# 05_LMS7002M_RF1.net
KiCad netlist of a schematic drawn in Altium Designer
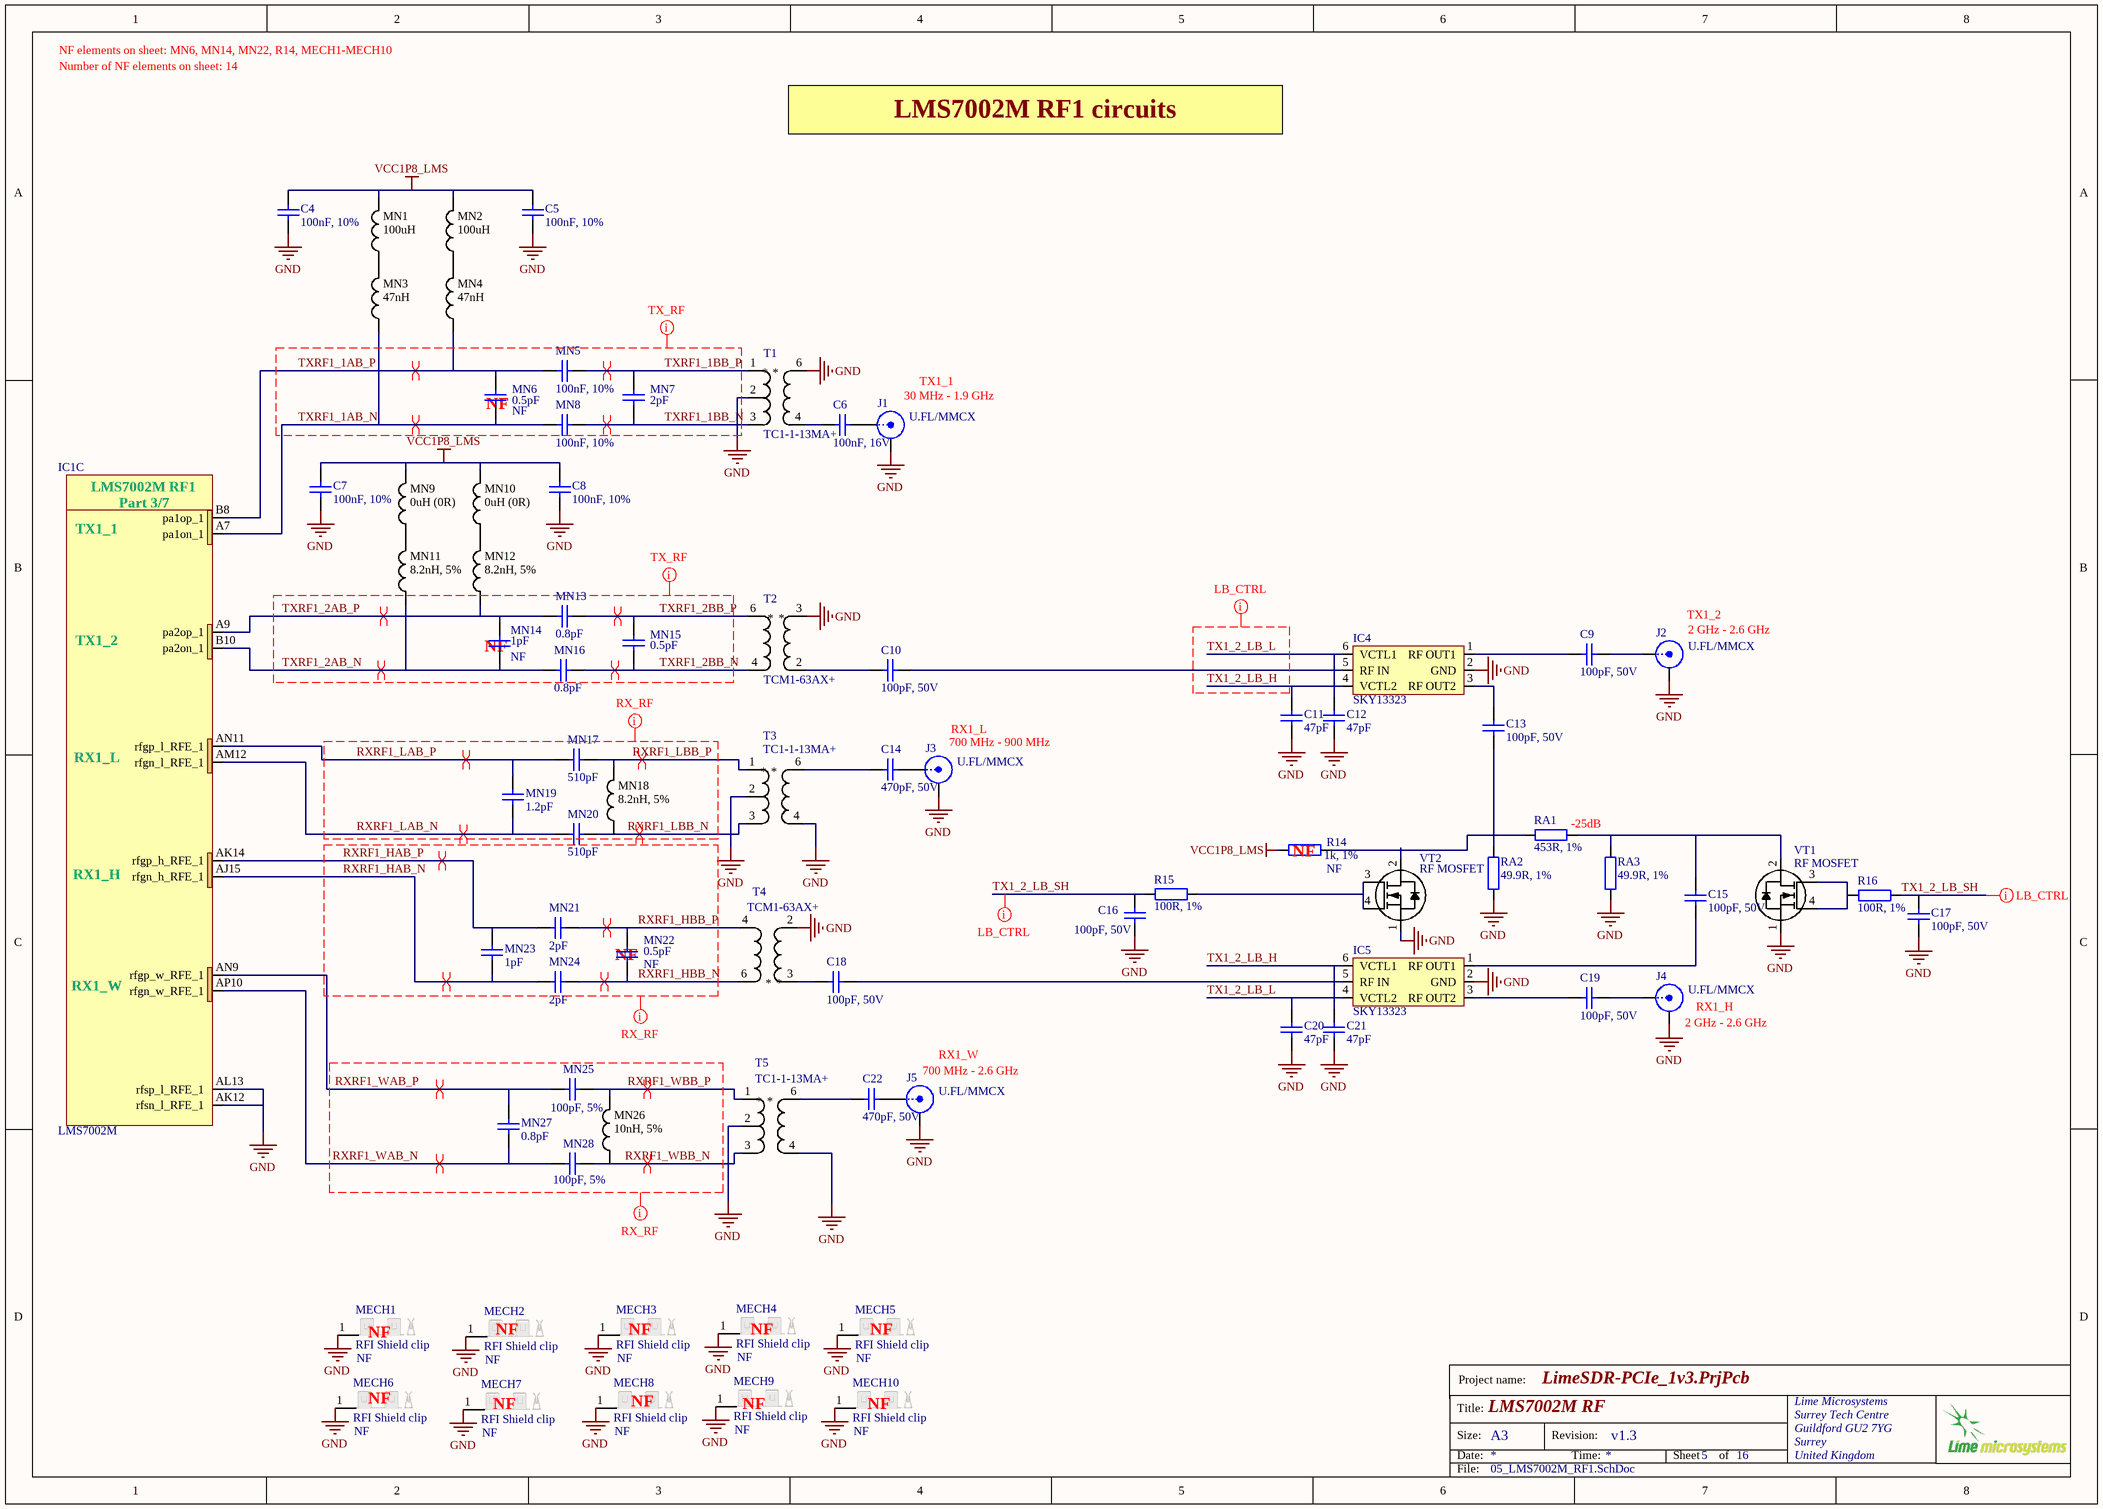
[diagram p0: 05_LMS7002M_RF1.SchDoc]

(export (version "E")
  (design (tool "Eeschema 10.0.6"))
  (components
    (comp (ref "C4")
      (value "100nF, 10%")
      (footprint "CAP0402")
      (fields
        (field (name "MANUFACTURER") "Murata Electronics")
        (field (name "TOLERANCE") "10 %")
        (field (name "MANUFACTURER PART NUMBER") "GRM155R71C104KA88D")
      )
      (libsource (lib "LimeMicroAltiumLib_schLib") (part "Cap_0402"))
    )
    (comp (ref "C5")
      (value "100nF, 10%")
      (footprint "CAP0402")
      (fields
        (field (name "MANUFACTURER") "Murata Electronics")
        (field (name "TOLERANCE") "10 %")
        (field (name "MANUFACTURER PART NUMBER") "GRM155R71C104KA88D")
      )
      (libsource (lib "LimeMicroAltiumLib_schLib") (part "Cap_0402"))
    )
    (comp (ref "C6")
      (value "100nF, 16V")
      (footprint "CAP0402")
      (fields
        (field (name "MANUFACTURER") "Murata Electronics")
        (field (name "TOLERANCE") "10 %")
        (field (name "MANUFACTURER PART NUMBER") "GRM155R71C104KA88D")
      )
      (libsource (lib "LimeMicroAltiumLib_schLib") (part "Cap_0402"))
    )
    (comp (ref "C7")
      (value "100nF, 10%")
      (footprint "CAP0402")
      (fields
        (field (name "MANUFACTURER") "Murata Electronics")
        (field (name "TOLERANCE") "10 %")
        (field (name "MANUFACTURER PART NUMBER") "GRM155R71C104KA88D")
      )
      (libsource (lib "LimeMicroAltiumLib_schLib") (part "Cap_0402"))
    )
    (comp (ref "C8")
      (value "100nF, 10%")
      (footprint "CAP0402")
      (fields
        (field (name "MANUFACTURER") "Murata Electronics")
        (field (name "TOLERANCE") "10 %")
        (field (name "MANUFACTURER PART NUMBER") "GRM155R71C104KA88D")
      )
      (libsource (lib "LimeMicroAltiumLib_schLib") (part "Cap_0402"))
    )
    (comp (ref "C9")
      (value "100pF, 50V")
      (footprint "CAP0402")
      (fields (field (name "TOLERANCE") "±5%") (field (name "MANUFACTURER") "Yageo"))
      (libsource (lib "LimeMicroAltiumLib_schLib") (part "Cap_0402"))
    )
    (comp (ref "C10")
      (value "100pF, 50V")
      (footprint "CAP0402")
      (fields (field (name "TOLERANCE") "±5%") (field (name "MANUFACTURER") "Yageo"))
      (libsource (lib "LimeMicroAltiumLib_schLib") (part "Cap_0402"))
    )
    (comp (ref "C11")
      (value "47pF")
      (footprint "CAP0402")
      (fields (field (name "TOLERANCE") "±1%") (field (name "MANUFACTURER") "TDK Corporation"))
      (libsource (lib "LimeMicroAltiumLib_schLib") (part "Cap_0402"))
    )
    (comp (ref "C12")
      (value "47pF")
      (footprint "CAP0402")
      (fields (field (name "TOLERANCE") "±1%") (field (name "MANUFACTURER") "TDK Corporation"))
      (libsource (lib "LimeMicroAltiumLib_schLib") (part "Cap_0402"))
    )
    (comp (ref "C13")
      (value "100pF, 50V")
      (footprint "CAP0402")
      (fields (field (name "TOLERANCE") "±5%") (field (name "MANUFACTURER") "Yageo"))
      (libsource (lib "LimeMicroAltiumLib_schLib") (part "Cap_0402"))
    )
    (comp (ref "C14")
      (value "470pF, 50V")
      (footprint "CAP0402")
      (fields
        (field (name "MANUFACTURER PART NUMBER") "C1005C0G1H471J050BA")
        (field (name "TOLERANCE") "±5%")
        (field (name "MANUFACTURER") "TDK Corporation")
      )
      (libsource (lib "LimeMicroAltiumLib_schLib") (part "Cap_0402"))
    )
    (comp (ref "C15")
      (value "100pF, 50V")
      (footprint "CAP0402")
      (fields (field (name "TOLERANCE") "±5%") (field (name "MANUFACTURER") "Yageo"))
      (libsource (lib "LimeMicroAltiumLib_schLib") (part "Cap_0402"))
    )
    (comp (ref "C16")
      (value "100pF, 50V")
      (footprint "CAP0402")
      (fields (field (name "TOLERANCE") "±5%") (field (name "MANUFACTURER") "Yageo"))
      (libsource (lib "LimeMicroAltiumLib_schLib") (part "Cap_0402"))
    )
    (comp (ref "C17")
      (value "100pF, 50V")
      (footprint "CAP0402")
      (fields (field (name "TOLERANCE") "±5%") (field (name "MANUFACTURER") "Yageo"))
      (libsource (lib "LimeMicroAltiumLib_schLib") (part "Cap_0402"))
    )
    (comp (ref "C18")
      (value "100pF, 50V")
      (footprint "CAP0402")
      (fields (field (name "TOLERANCE") "±5%") (field (name "MANUFACTURER") "Yageo"))
      (libsource (lib "LimeMicroAltiumLib_schLib") (part "Cap_0402"))
    )
    (comp (ref "C19")
      (value "100pF, 50V")
      (footprint "CAP0402")
      (fields (field (name "TOLERANCE") "±5%") (field (name "MANUFACTURER") "Yageo"))
      (libsource (lib "LimeMicroAltiumLib_schLib") (part "Cap_0402"))
    )
    (comp (ref "C20")
      (value "47pF")
      (footprint "CAP0402")
      (fields (field (name "TOLERANCE") "±1%") (field (name "MANUFACTURER") "TDK Corporation"))
      (libsource (lib "LimeMicroAltiumLib_schLib") (part "Cap_0402"))
    )
    (comp (ref "C21")
      (value "47pF")
      (footprint "CAP0402")
      (fields (field (name "TOLERANCE") "±1%") (field (name "MANUFACTURER") "TDK Corporation"))
      (libsource (lib "LimeMicroAltiumLib_schLib") (part "Cap_0402"))
    )
    (comp (ref "C22")
      (value "470pF, 50V")
      (footprint "CAP0402")
      (fields
        (field (name "MANUFACTURER PART NUMBER") "C1005C0G1H471J050BA")
        (field (name "TOLERANCE") "±5%")
        (field (name "MANUFACTURER") "TDK Corporation")
      )
      (libsource (lib "LimeMicroAltiumLib_schLib") (part "Cap_0402"))
    )
    (comp (ref "IC1")
      (value "LMS7002M")
      (footprint "LMS7002M_v2")
      (description "Schematic symbol revision 3. Default footprint - 0.31mm pad")
      (fields (field (name "MANUFACTURER") "Lime Microsystems"))
      (libsource (lib "LimeMicroAltiumLib_schLib") (part "LMS7002Mr3"))
    )
    (comp (ref "IC4")
      (value "SKY13323")
      (footprint "SKY13323-378LF")
      (description "SKY13323-378LF: 0.1-3.0 GHz GaAs SPDT Switch")
      (fields (field (name "MANUFACTURER") "Skyworks Solutions Inc."))
      (libsource (lib "LimeMicroAltiumLib_schLib") (part "SKY13323"))
    )
    (comp (ref "IC5")
      (value "SKY13323")
      (footprint "SKY13323-378LF")
      (description "SKY13323-378LF: 0.1-3.0 GHz GaAs SPDT Switch")
      (fields (field (name "MANUFACTURER") "Skyworks Solutions Inc."))
      (libsource (lib "LimeMicroAltiumLib_schLib") (part "SKY13323"))
    )
    (comp (ref "J1")
      (value "U.FL/MMCX")
      (footprint "MMCX_UFL_conn_u")
      (description "CONN UMC RCPT STR 50 OHM SMD")
      (fields (field (name "MANUFACTURER") "Molex, LLC"))
      (libsource (lib "LimeMicroAltiumLib_schLib") (part "RF_IF_connector"))
    )
    (comp (ref "J2")
      (value "U.FL/MMCX")
      (footprint "MMCX_UFL_conn_u")
      (description "CONN UMC RCPT STR 50 OHM SMD")
      (fields (field (name "MANUFACTURER") "Molex, LLC"))
      (libsource (lib "LimeMicroAltiumLib_schLib") (part "RF_IF_connector"))
    )
    (comp (ref "J3")
      (value "U.FL/MMCX")
      (footprint "MMCX_UFL_conn_u")
      (description "CONN UMC RCPT STR 50 OHM SMD")
      (fields (field (name "MANUFACTURER") "Molex, LLC"))
      (libsource (lib "LimeMicroAltiumLib_schLib") (part "RF_IF_connector"))
    )
    (comp (ref "J4")
      (value "U.FL/MMCX")
      (footprint "MMCX_UFL_conn_u")
      (description "CONN UMC RCPT STR 50 OHM SMD")
      (fields (field (name "MANUFACTURER") "Molex, LLC"))
      (libsource (lib "LimeMicroAltiumLib_schLib") (part "RF_IF_connector"))
    )
    (comp (ref "J5")
      (value "U.FL/MMCX")
      (footprint "MMCX_UFL_conn_u")
      (description "CONN UMC RCPT STR 50 OHM SMD")
      (fields (field (name "MANUFACTURER") "Molex, LLC"))
      (libsource (lib "LimeMicroAltiumLib_schLib") (part "RF_IF_connector"))
    )
    (comp (ref "MECH1")
      (value "RFI Shield clip")
      (footprint "RFI_SHIELD_CLPS_MINI")
      (fields (field (name "MANUFACTURER") "HARWIN") (field (name "ASSEMBLY INFO") "NF"))
      (libsource (lib "LimeMicroAltiumLib_schLib") (part "RFI_SHIELD_CLIP"))
    )
    (comp (ref "MECH2")
      (value "RFI Shield clip")
      (footprint "RFI_SHIELD_CLPS_MINI")
      (fields (field (name "MANUFACTURER") "HARWIN") (field (name "ASSEMBLY INFO") "NF"))
      (libsource (lib "LimeMicroAltiumLib_schLib") (part "RFI_SHIELD_CLIP"))
    )
    (comp (ref "MECH3")
      (value "RFI Shield clip")
      (footprint "RFI_SHIELD_CLPS_MINI")
      (fields (field (name "MANUFACTURER") "HARWIN") (field (name "ASSEMBLY INFO") "NF"))
      (libsource (lib "LimeMicroAltiumLib_schLib") (part "RFI_SHIELD_CLIP"))
    )
    (comp (ref "MECH4")
      (value "RFI Shield clip")
      (footprint "RFI_SHIELD_CLPS_MINI")
      (fields (field (name "MANUFACTURER") "HARWIN") (field (name "ASSEMBLY INFO") "NF"))
      (libsource (lib "LimeMicroAltiumLib_schLib") (part "RFI_SHIELD_CLIP"))
    )
    (comp (ref "MECH5")
      (value "RFI Shield clip")
      (footprint "RFI_SHIELD_CLPS_MINI")
      (fields (field (name "MANUFACTURER") "HARWIN") (field (name "ASSEMBLY INFO") "NF"))
      (libsource (lib "LimeMicroAltiumLib_schLib") (part "RFI_SHIELD_CLIP"))
    )
    (comp (ref "MECH6")
      (value "RFI Shield clip")
      (footprint "RFI_SHIELD_CLPS_MINI")
      (fields (field (name "MANUFACTURER") "HARWIN") (field (name "ASSEMBLY INFO") "NF"))
      (libsource (lib "LimeMicroAltiumLib_schLib") (part "RFI_SHIELD_CLIP"))
    )
    (comp (ref "MECH7")
      (value "RFI Shield clip")
      (footprint "RFI_SHIELD_CLPS_MINI")
      (fields (field (name "MANUFACTURER") "HARWIN") (field (name "ASSEMBLY INFO") "NF"))
      (libsource (lib "LimeMicroAltiumLib_schLib") (part "RFI_SHIELD_CLIP"))
    )
    (comp (ref "MECH8")
      (value "RFI Shield clip")
      (footprint "RFI_SHIELD_CLPS_MINI")
      (fields (field (name "MANUFACTURER") "HARWIN") (field (name "ASSEMBLY INFO") "NF"))
      (libsource (lib "LimeMicroAltiumLib_schLib") (part "RFI_SHIELD_CLIP"))
    )
    (comp (ref "MECH9")
      (value "RFI Shield clip")
      (footprint "RFI_SHIELD_CLPS_MINI")
      (fields (field (name "MANUFACTURER") "HARWIN") (field (name "ASSEMBLY INFO") "NF"))
      (libsource (lib "LimeMicroAltiumLib_schLib") (part "RFI_SHIELD_CLIP"))
    )
    (comp (ref "MECH10")
      (value "RFI Shield clip")
      (footprint "RFI_SHIELD_CLPS_MINI")
      (fields (field (name "MANUFACTURER") "HARWIN") (field (name "ASSEMBLY INFO") "NF"))
      (libsource (lib "LimeMicroAltiumLib_schLib") (part "RFI_SHIELD_CLIP"))
    )
    (comp (ref "MN1")
      (value "100uH")
      (footprint "RES0805")
      (fields
        (field (name "TOLERANCE") "±10%")
        (field (name "MANUFACTURER") "TDK Corporation")
        (field (name "MANUFACTURER PART NUMBER") "MLF2012C101KT000")
      )
      (libsource (lib "LimeMicroAltiumLib_schLib") (part "Inductor_0603"))
    )
    (comp (ref "MN2")
      (value "100uH")
      (footprint "RES0805")
      (fields
        (field (name "TOLERANCE") "±10%")
        (field (name "MANUFACTURER") "TDK Corporation")
        (field (name "MANUFACTURER PART NUMBER") "MLF2012C101KT000")
      )
      (libsource (lib "LimeMicroAltiumLib_schLib") (part "Inductor_0603"))
    )
    (comp (ref "MN3")
      (value "47nH")
      (footprint "RES0402")
      (fields
        (field (name "MANUFACTURER") "COILCRAFT")
        (field (name "MANUFACTURER PART NUMBER") "0402HP-47NXJLU")
      )
      (libsource (lib "LimeMicroAltiumLib_schLib") (part "Inductor_0603"))
    )
    (comp (ref "MN4")
      (value "47nH")
      (footprint "RES0402")
      (fields
        (field (name "MANUFACTURER") "COILCRAFT")
        (field (name "MANUFACTURER PART NUMBER") "0402HP-47NXJLU")
      )
      (libsource (lib "LimeMicroAltiumLib_schLib") (part "Inductor_0603"))
    )
    (comp (ref "MN5")
      (value "100nF, 10%")
      (footprint "CAP0402")
      (fields
        (field (name "MANUFACTURER") "Murata Electronics")
        (field (name "TOLERANCE") "10 %")
        (field (name "MANUFACTURER PART NUMBER") "GRM155R71C104KA88D")
      )
      (libsource (lib "LimeMicroAltiumLib_schLib") (part "Cap_0402"))
    )
    (comp (ref "MN6")
      (value "0.5pF")
      (footprint "CAP0402")
      (fields
        (field (name "ASSEMBLY INFO") "NF")
        (field (name "TOLERANCE") "±0.25pF")
        (field (name "MANUFACTURER") "Yageo")
      )
      (libsource (lib "LimeMicroAltiumLib_schLib") (part "Cap_0402"))
    )
    (comp (ref "MN7")
      (value "2pF")
      (footprint "CAP0402")
      (fields (field (name "MANUFACTURER PART NUMBER") "04025U2R0BAT2A") (field (name "MANUFACTURER") "AVX"))
      (libsource (lib "LimeMicroAltiumLib_schLib") (part "Cap_0402"))
    )
    (comp (ref "MN8")
      (value "100nF, 10%")
      (footprint "CAP0402")
      (fields
        (field (name "MANUFACTURER") "Murata Electronics")
        (field (name "TOLERANCE") "10 %")
        (field (name "MANUFACTURER PART NUMBER") "GRM155R71C104KA88D")
      )
      (libsource (lib "LimeMicroAltiumLib_schLib") (part "Cap_0402"))
    )
    (comp (ref "MN9")
      (value "0uH (0R)")
      (footprint "RES0805")
      (fields
        (field (name "MANUFACTURER") "BOURNS")
        (field (name "MANUFACTURER PART NUMBER") "CR0805-J/-000ELF")
      )
      (libsource (lib "LimeMicroAltiumLib_schLib") (part "Inductor_0603"))
    )
    (comp (ref "MN10")
      (value "0uH (0R)")
      (footprint "RES0805")
      (fields
        (field (name "MANUFACTURER") "BOURNS")
        (field (name "MANUFACTURER PART NUMBER") "CR0805-J/-000ELF")
      )
      (libsource (lib "LimeMicroAltiumLib_schLib") (part "Inductor_0603"))
    )
    (comp (ref "MN11")
      (value "8.2nH, 5%")
      (footprint "RES0402")
      (fields (field (name "MANUFACTURER") "COILCRAFT"))
      (libsource (lib "LimeMicroAltiumLib_schLib") (part "Inductor_0603"))
    )
    (comp (ref "MN12")
      (value "8.2nH, 5%")
      (footprint "RES0402")
      (fields (field (name "MANUFACTURER") "COILCRAFT"))
      (libsource (lib "LimeMicroAltiumLib_schLib") (part "Inductor_0603"))
    )
    (comp (ref "MN13")
      (value "0.8pF")
      (footprint "CAP0402")
      (fields
        (field (name "TOLERANCE") "±0.1pF")
        (field (name "MANUFACTURER") "Murata Electronics North America")
        (field (name "MANUFACTURER PART NUMBER") "GRM1555C1HR80BA01D")
      )
      (libsource (lib "LimeMicroAltiumLib_schLib") (part "Cap_0402"))
    )
    (comp (ref "MN14")
      (value "1pF")
      (footprint "CAP0402")
      (fields
        (field (name "ASSEMBLY INFO") "NF")
        (field (name "MANUFACTURER") "TDK Corporation")
        (field (name "TOLERANCE") "±0.1pF")
      )
      (libsource (lib "LimeMicroAltiumLib_schLib") (part "Cap_0402"))
    )
    (comp (ref "MN15")
      (value "0.5pF")
      (footprint "CAP0402")
      (fields (field (name "TOLERANCE") "±0.25pF") (field (name "MANUFACTURER") "Yageo"))
      (libsource (lib "LimeMicroAltiumLib_schLib") (part "Cap_0402"))
    )
    (comp (ref "MN16")
      (value "0.8pF")
      (footprint "CAP0402")
      (fields
        (field (name "TOLERANCE") "±0.1pF")
        (field (name "MANUFACTURER") "Murata Electronics North America")
        (field (name "MANUFACTURER PART NUMBER") "GRM1555C1HR80BA01D")
      )
      (libsource (lib "LimeMicroAltiumLib_schLib") (part "Cap_0402"))
    )
    (comp (ref "MN17")
      (value "510pF")
      (footprint "CAP0402")
      (fields
        (field (name "TOLERANCE") "±5%")
        (field (name "MANUFACTURER") "Murata Electronics North America")
        (field (name "MANUFACTURER PART NUMBER") "GRM1555C1H511JA01D")
      )
      (libsource (lib "LimeMicroAltiumLib_schLib") (part "Cap_0402"))
    )
    (comp (ref "MN18")
      (value "8.2nH, 5%")
      (footprint "RES0402")
      (fields (field (name "MANUFACTURER") "COILCRAFT"))
      (libsource (lib "LimeMicroAltiumLib_schLib") (part "Inductor_0603"))
    )
    (comp (ref "MN19")
      (value "1.2pF")
      (footprint "CAP0402")
      (fields
        (field (name "MANUFACTURER") "Murata Electronics North America")
        (field (name "MANUFACTURER PART NUMBER") "GRM1555C1H1R2CA01D")
        (field (name "TOLERANCE") "±0.25pF")
      )
      (libsource (lib "LimeMicroAltiumLib_schLib") (part "Cap_0402"))
    )
    (comp (ref "MN20")
      (value "510pF")
      (footprint "CAP0402")
      (fields
        (field (name "TOLERANCE") "±5%")
        (field (name "MANUFACTURER") "Murata Electronics North America")
        (field (name "MANUFACTURER PART NUMBER") "GRM1555C1H511JA01D")
      )
      (libsource (lib "LimeMicroAltiumLib_schLib") (part "Cap_0402"))
    )
    (comp (ref "MN21")
      (value "2pF")
      (footprint "CAP0402")
      (fields (field (name "MANUFACTURER PART NUMBER") "04025U2R0BAT2A") (field (name "MANUFACTURER") "AVX"))
      (libsource (lib "LimeMicroAltiumLib_schLib") (part "Cap_0402"))
    )
    (comp (ref "MN22")
      (value "0.5pF")
      (footprint "CAP0402")
      (fields
        (field (name "ASSEMBLY INFO") "NF")
        (field (name "TOLERANCE") "±0.25pF")
        (field (name "MANUFACTURER") "Yageo")
      )
      (libsource (lib "LimeMicroAltiumLib_schLib") (part "Cap_0402"))
    )
    (comp (ref "MN23")
      (value "1pF")
      (footprint "CAP0402")
      (fields (field (name "MANUFACTURER") "TDK Corporation") (field (name "TOLERANCE") "±0.1pF"))
      (libsource (lib "LimeMicroAltiumLib_schLib") (part "Cap_0402"))
    )
    (comp (ref "MN24")
      (value "2pF")
      (footprint "CAP0402")
      (fields (field (name "MANUFACTURER PART NUMBER") "04025U2R0BAT2A") (field (name "MANUFACTURER") "AVX"))
      (libsource (lib "LimeMicroAltiumLib_schLib") (part "Cap_0402"))
    )
    (comp (ref "MN25")
      (value "100pF, 5%")
      (footprint "CAP0402")
      (fields (field (name "TOLERANCE") "±5%") (field (name "MANUFACTURER") "Yageo"))
      (libsource (lib "LimeMicroAltiumLib_schLib") (part "Cap_0402"))
    )
    (comp (ref "MN26")
      (value "10nH, 5%")
      (footprint "RES0402")
      (fields (field (name "MANUFACTURER") "COILCRAFT"))
      (libsource (lib "LimeMicroAltiumLib_schLib") (part "Inductor_0603"))
    )
    (comp (ref "MN27")
      (value "0.8pF")
      (footprint "CAP0402")
      (fields
        (field (name "TOLERANCE") "±0.1pF")
        (field (name "MANUFACTURER") "Murata Electronics North America")
        (field (name "MANUFACTURER PART NUMBER") "GRM1555C1HR80BA01D")
      )
      (libsource (lib "LimeMicroAltiumLib_schLib") (part "Cap_0402"))
    )
    (comp (ref "MN28")
      (value "100pF, 5%")
      (footprint "CAP0402")
      (fields (field (name "TOLERANCE") "±5%") (field (name "MANUFACTURER") "Yageo"))
      (libsource (lib "LimeMicroAltiumLib_schLib") (part "Cap_0402"))
    )
    (comp (ref "R14")
      (value "1k, 1%")
      (footprint "RES0402")
      (fields
        (field (name "ASSEMBLY INFO") "NF")
        (field (name "MANUFACTURER") "Stackpole Electronics Inc")
        (field (name "TOLERANCE") "±1%")
      )
      (libsource (lib "LimeMicroAltiumLib_schLib") (part "Res_0402"))
    )
    (comp (ref "R15")
      (value "100R, 1%")
      (footprint "RES0402")
      (fields (field (name "TOLERANCE") "±1%") (field (name "MANUFACTURER") "Stackpole Electronics Inc."))
      (libsource (lib "LimeFPGAboard_schLib") (part "Res_0402"))
    )
    (comp (ref "R16")
      (value "100R, 1%")
      (footprint "RES0402")
      (fields (field (name "TOLERANCE") "±1%") (field (name "MANUFACTURER") "Stackpole Electronics Inc."))
      (libsource (lib "LimeFPGAboard_schLib") (part "Res_0402"))
    )
    (comp (ref "RA1")
      (value "453R, 1%")
      (footprint "RES0402")
      (fields (field (name "MANUFACTURER") "Yageo") (field (name "TOLERANCE") "±1%"))
      (libsource (lib "LimeMicroAltiumLib_schLib") (part "Res_0402"))
    )
    (comp (ref "RA2")
      (value "49.9R, 1%")
      (footprint "RES0402")
      (fields
        (field (name "TOLERANCE") "±1%")
        (field (name "MANUFACTURER") "Samsung Electro-Mechanics America, Inc.")
        (field (name "MANUFACTURER PART NUMBER") "RC1005F49R9CS")
      )
      (libsource (lib "LimeMicroAltiumLib_schLib") (part "Res_0402"))
    )
    (comp (ref "RA3")
      (value "49.9R, 1%")
      (footprint "RES0402")
      (fields
        (field (name "TOLERANCE") "±1%")
        (field (name "MANUFACTURER") "Samsung Electro-Mechanics America, Inc.")
        (field (name "MANUFACTURER PART NUMBER") "RC1005F49R9CS")
      )
      (libsource (lib "LimeMicroAltiumLib_schLib") (part "Res_0402"))
    )
    (comp (ref "T1")
      (value "TC1-1-13MA+")
      (footprint "TC1-1-13MA+_v2")
      (fields (field (name "MANUFACTURER") "Mini-Circuits"))
      (libsource (lib "LimeMicroAltiumLib_schLib") (part "Balun"))
    )
    (comp (ref "T2")
      (value "TCM1-63AX+")
      (footprint "TCM1-63AX+_v2")
      (fields (field (name "MANUFACTURER") "Mini-circuits"))
      (libsource (lib "LimeMicroAltiumLib_schLib") (part "Balun_v2"))
    )
    (comp (ref "T3")
      (value "TC1-1-13MA+")
      (footprint "TC1-1-13MA+_v2")
      (fields (field (name "MANUFACTURER") "Mini-Circuits"))
      (libsource (lib "LimeMicroAltiumLib_schLib") (part "Balun"))
    )
    (comp (ref "T4")
      (value "TCM1-63AX+")
      (footprint "TCM1-63AX+_v2")
      (fields (field (name "MANUFACTURER") "Mini-circuits"))
      (libsource (lib "") (part "Balun_v2_1"))
    )
    (comp (ref "T5")
      (value "TC1-1-13MA+")
      (footprint "TC1-1-13MA+_v2")
      (fields (field (name "MANUFACTURER") "Mini-Circuits"))
      (libsource (lib "LimeMicroAltiumLib_schLib") (part "Balun"))
    )
    (comp (ref "VT1")
      (value "RF MOSFET")
      (footprint "BF1105R_SOT143R4")
      (fields (field (name "MANUFACTURER") "NXP Semiconductors"))
      (libsource (lib "LimeMicroAltiumLib_schLib") (part "BF1105R,215"))
    )
    (comp (ref "VT2")
      (value "RF MOSFET")
      (footprint "BF1105R_SOT143R4")
      (fields (field (name "MANUFACTURER") "NXP Semiconductors"))
      (libsource (lib "LimeMicroAltiumLib_schLib") (part "BF1105R,215"))
    )
  )
  (nets
    (net (code "1") (name "/RXRF1_HAB_N") (class "Default")
      (node (ref "IC1") (pin "AJ15") (pinfunction "rfgn_h_RFE_1_AJ15") (pintype "passive"))
      (node (ref "MN23") (pin "1") (pinfunction "1_1") (pintype "passive"))
      (node (ref "MN24") (pin "2") (pinfunction "2_2") (pintype "passive"))
    )
    (net (code "2") (name "/RXRF1_HAB_P") (class "Default")
      (node (ref "IC1") (pin "AK14") (pinfunction "rfgp_h_RFE_1_AK14") (pintype "passive"))
      (node (ref "MN21") (pin "2") (pinfunction "2_2") (pintype "passive"))
      (node (ref "MN23") (pin "2") (pinfunction "2_2") (pintype "passive"))
    )
    (net (code "3") (name "/RXRF1_HBB_N") (class "Default")
      (node (ref "MN22") (pin "1") (pinfunction "1_1") (pintype "passive"))
      (node (ref "MN24") (pin "1") (pinfunction "1_1") (pintype "passive"))
      (node (ref "T4") (pin "6") (pinfunction "6_6") (pintype "passive"))
    )
    (net (code "4") (name "/RXRF1_HBB_P") (class "Default")
      (node (ref "MN21") (pin "1") (pinfunction "1_1") (pintype "passive"))
      (node (ref "MN22") (pin "2") (pinfunction "2_2") (pintype "passive"))
      (node (ref "T4") (pin "4") (pinfunction "4_4") (pintype "passive"))
    )
    (net (code "5") (name "/RXRF1_LAB_N") (class "Default")
      (node (ref "IC1") (pin "AM12") (pinfunction "rfgn_l_RFE_1_AM12") (pintype "passive"))
      (node (ref "MN19") (pin "1") (pinfunction "1_1") (pintype "passive"))
      (node (ref "MN20") (pin "2") (pinfunction "2_2") (pintype "passive"))
    )
    (net (code "6") (name "/RXRF1_LAB_P") (class "Default")
      (node (ref "IC1") (pin "AN11") (pinfunction "rfgp_l_RFE_1_AN11") (pintype "passive"))
      (node (ref "MN17") (pin "2") (pinfunction "2_2") (pintype "passive"))
      (node (ref "MN19") (pin "2") (pinfunction "2_2") (pintype "passive"))
    )
    (net (code "7") (name "/RXRF1_LBB_N") (class "Default")
      (node (ref "MN18") (pin "1") (pinfunction "1_1") (pintype "passive"))
      (node (ref "MN20") (pin "1") (pinfunction "1_1") (pintype "passive"))
      (node (ref "T3") (pin "3") (pinfunction "3_3") (pintype "passive"))
    )
    (net (code "8") (name "/RXRF1_LBB_P") (class "Default")
      (node (ref "MN17") (pin "1") (pinfunction "1_1") (pintype "passive"))
      (node (ref "MN18") (pin "2") (pinfunction "2_2") (pintype "passive"))
      (node (ref "T3") (pin "1") (pinfunction "1_1") (pintype "passive"))
    )
    (net (code "9") (name "/RXRF1_WAB_N") (class "Default")
      (node (ref "IC1") (pin "AP10") (pinfunction "rfgn_w_RFE_1_AP10") (pintype "passive"))
      (node (ref "MN27") (pin "2") (pinfunction "2_2") (pintype "passive"))
      (node (ref "MN28") (pin "2") (pinfunction "2_2") (pintype "passive"))
    )
    (net (code "10") (name "/RXRF1_WAB_P") (class "Default")
      (node (ref "IC1") (pin "AN9") (pinfunction "rfgp_w_RFE_1_AN9") (pintype "passive"))
      (node (ref "MN25") (pin "2") (pinfunction "2_2") (pintype "passive"))
      (node (ref "MN27") (pin "1") (pinfunction "1_1") (pintype "passive"))
    )
    (net (code "11") (name "/RXRF1_WBB_N") (class "Default")
      (node (ref "MN26") (pin "1") (pinfunction "1_1") (pintype "passive"))
      (node (ref "MN28") (pin "1") (pinfunction "1_1") (pintype "passive"))
      (node (ref "T5") (pin "3") (pinfunction "3_3") (pintype "passive"))
    )
    (net (code "12") (name "/RXRF1_WBB_P") (class "Default")
      (node (ref "MN25") (pin "1") (pinfunction "1_1") (pintype "passive"))
      (node (ref "MN26") (pin "2") (pinfunction "2_2") (pintype "passive"))
      (node (ref "T5") (pin "1") (pinfunction "1_1") (pintype "passive"))
    )
    (net (code "13") (name "/TX1_2_LB_H") (class "Default")
      (node (ref "C11") (pin "2") (pinfunction "2_2") (pintype "passive"))
      (node (ref "C21") (pin "2") (pinfunction "2_2") (pintype "passive"))
      (node (ref "IC4") (pin "4") (pinfunction "VCTL2_4") (pintype "input"))
      (node (ref "IC5") (pin "6") (pinfunction "VCTL1_6") (pintype "input"))
    )
    (net (code "14") (name "/TX1_2_LB_L") (class "Default")
      (node (ref "C12") (pin "2") (pinfunction "2_2") (pintype "passive"))
      (node (ref "C20") (pin "2") (pinfunction "2_2") (pintype "passive"))
      (node (ref "IC4") (pin "6") (pinfunction "VCTL1_6") (pintype "input"))
      (node (ref "IC5") (pin "4") (pinfunction "VCTL2_4") (pintype "input"))
    )
    (net (code "15") (name "/TX1_2_LB_SH") (class "Default")
      (node (ref "C16") (pin "1") (pinfunction "1_1") (pintype "passive"))
      (node (ref "C17") (pin "1") (pinfunction "1_1") (pintype "passive"))
      (node (ref "R15") (pin "2") (pinfunction "2_2") (pintype "passive"))
      (node (ref "R16") (pin "1") (pinfunction "1_1") (pintype "passive"))
    )
    (net (code "16") (name "/TXRF1_1AB_N") (class "Default")
      (node (ref "IC1") (pin "A7") (pinfunction "pa1on_1_A7") (pintype "passive"))
      (node (ref "MN3") (pin "1") (pinfunction "1_1") (pintype "passive"))
      (node (ref "MN6") (pin "1") (pinfunction "1_1") (pintype "passive"))
      (node (ref "MN8") (pin "1") (pinfunction "1_1") (pintype "passive"))
    )
    (net (code "17") (name "/TXRF1_1AB_P") (class "Default")
      (node (ref "IC1") (pin "B8") (pinfunction "pa1op_1_B8") (pintype "passive"))
      (node (ref "MN4") (pin "1") (pinfunction "1_1") (pintype "passive"))
      (node (ref "MN5") (pin "2") (pinfunction "2_2") (pintype "passive"))
      (node (ref "MN6") (pin "2") (pinfunction "2_2") (pintype "passive"))
    )
    (net (code "18") (name "/TXRF1_1BB_N") (class "Default")
      (node (ref "MN7") (pin "1") (pinfunction "1_1") (pintype "passive"))
      (node (ref "MN8") (pin "2") (pinfunction "2_2") (pintype "passive"))
      (node (ref "T1") (pin "3") (pinfunction "3_3") (pintype "passive"))
    )
    (net (code "19") (name "/TXRF1_1BB_P") (class "Default")
      (node (ref "MN5") (pin "1") (pinfunction "1_1") (pintype "passive"))
      (node (ref "MN7") (pin "2") (pinfunction "2_2") (pintype "passive"))
      (node (ref "T1") (pin "1") (pinfunction "1_1") (pintype "passive"))
    )
    (net (code "20") (name "/TXRF1_2AB_N") (class "Default")
      (node (ref "IC1") (pin "B10") (pinfunction "pa2on_1_B10") (pintype "passive"))
      (node (ref "MN11") (pin "1") (pinfunction "1_1") (pintype "passive"))
      (node (ref "MN14") (pin "2") (pinfunction "2_2") (pintype "passive"))
      (node (ref "MN16") (pin "2") (pinfunction "2_2") (pintype "passive"))
    )
    (net (code "21") (name "/TXRF1_2AB_P") (class "Default")
      (node (ref "IC1") (pin "A9") (pinfunction "pa2op_1_A9") (pintype "passive"))
      (node (ref "MN12") (pin "1") (pinfunction "1_1") (pintype "passive"))
      (node (ref "MN13") (pin "2") (pinfunction "2_2") (pintype "passive"))
      (node (ref "MN14") (pin "1") (pinfunction "1_1") (pintype "passive"))
    )
    (net (code "22") (name "/TXRF1_2BB_N") (class "Default")
      (node (ref "MN15") (pin "1") (pinfunction "1_1") (pintype "passive"))
      (node (ref "MN16") (pin "1") (pinfunction "1_1") (pintype "passive"))
      (node (ref "T2") (pin "4") (pinfunction "4_4") (pintype "passive"))
    )
    (net (code "23") (name "/TXRF1_2BB_P") (class "Default")
      (node (ref "MN13") (pin "1") (pinfunction "1_1") (pintype "passive"))
      (node (ref "MN15") (pin "2") (pinfunction "2_2") (pintype "passive"))
      (node (ref "T2") (pin "6") (pinfunction "6_6") (pintype "passive"))
    )
    (net (code "24") (name "GND") (class "Default")
      (node (ref "C11") (pin "1") (pinfunction "1_1") (pintype "passive"))
      (node (ref "C12") (pin "1") (pinfunction "1_1") (pintype "passive"))
      (node (ref "C16") (pin "2") (pinfunction "2_2") (pintype "passive"))
      (node (ref "C17") (pin "2") (pinfunction "2_2") (pintype "passive"))
      (node (ref "C20") (pin "1") (pinfunction "1_1") (pintype "passive"))
      (node (ref "C21") (pin "1") (pinfunction "1_1") (pintype "passive"))
      (node (ref "C4") (pin "1") (pinfunction "1_1") (pintype "passive"))
      (node (ref "C5") (pin "1") (pinfunction "1_1") (pintype "passive"))
      (node (ref "C7") (pin "1") (pinfunction "1_1") (pintype "passive"))
      (node (ref "C8") (pin "1") (pinfunction "1_1") (pintype "passive"))
      (node (ref "IC1") (pin "AK12") (pinfunction "rfsn_l_RFE_1_AK12") (pintype "passive"))
      (node (ref "IC1") (pin "AL13") (pinfunction "rfsp_l_RFE_1_AL13") (pintype "passive"))
      (node (ref "IC4") (pin "2") (pinfunction "GND_2") (pintype "passive"))
      (node (ref "IC5") (pin "2") (pinfunction "GND_2") (pintype "passive"))
      (node (ref "J1") (pin "2") (pinfunction "Y_2") (pintype "passive"))
      (node (ref "J2") (pin "2") (pinfunction "Y_2") (pintype "passive"))
      (node (ref "J3") (pin "2") (pinfunction "Y_2") (pintype "passive"))
      (node (ref "J4") (pin "2") (pinfunction "Y_2") (pintype "passive"))
      (node (ref "J5") (pin "2") (pinfunction "Y_2") (pintype "passive"))
      (node (ref "MECH1") (pin "1") (pinfunction "GND_1") (pintype "passive"))
      (node (ref "MECH10") (pin "1") (pinfunction "GND_1") (pintype "passive"))
      (node (ref "MECH2") (pin "1") (pinfunction "GND_1") (pintype "passive"))
      (node (ref "MECH3") (pin "1") (pinfunction "GND_1") (pintype "passive"))
      (node (ref "MECH4") (pin "1") (pinfunction "GND_1") (pintype "passive"))
      (node (ref "MECH5") (pin "1") (pinfunction "GND_1") (pintype "passive"))
      (node (ref "MECH6") (pin "1") (pinfunction "GND_1") (pintype "passive"))
      (node (ref "MECH7") (pin "1") (pinfunction "GND_1") (pintype "passive"))
      (node (ref "MECH8") (pin "1") (pinfunction "GND_1") (pintype "passive"))
      (node (ref "MECH9") (pin "1") (pinfunction "GND_1") (pintype "passive"))
      (node (ref "RA2") (pin "1") (pinfunction "1_1") (pintype "passive"))
      (node (ref "RA3") (pin "1") (pinfunction "1_1") (pintype "passive"))
      (node (ref "T1") (pin "2") (pinfunction "2_2") (pintype "passive"))
      (node (ref "T1") (pin "6") (pinfunction "6_6") (pintype "passive"))
      (node (ref "T2") (pin "3") (pinfunction "3_3") (pintype "passive"))
      (node (ref "T3") (pin "2") (pinfunction "2_2") (pintype "passive"))
      (node (ref "T3") (pin "4") (pinfunction "4_4") (pintype "passive"))
      (node (ref "T4") (pin "2") (pinfunction "2_2") (pintype "passive"))
      (node (ref "T5") (pin "2") (pinfunction "2_2") (pintype "passive"))
      (node (ref "T5") (pin "4") (pinfunction "4_4") (pintype "passive"))
      (node (ref "VT1") (pin "1") (pinfunction "S_1") (pintype "passive"))
      (node (ref "VT2") (pin "1") (pinfunction "S_1") (pintype "passive"))
    )
    (net (code "25") (name "Net-(C6-Pad2)") (class "Default")
      (node (ref "C6") (pin "2") (pinfunction "2_2") (pintype "passive"))
      (node (ref "T1") (pin "4") (pinfunction "4_4") (pintype "passive"))
    )
    (net (code "26") (name "Net-(C10-Pad2)") (class "Default")
      (node (ref "C10") (pin "2") (pinfunction "2_2") (pintype "passive"))
      (node (ref "T2") (pin "2") (pinfunction "2_2") (pintype "passive"))
    )
    (net (code "27") (name "Net-(C14-Pad2)") (class "Default")
      (node (ref "C14") (pin "2") (pinfunction "2_2") (pintype "passive"))
      (node (ref "T3") (pin "6") (pinfunction "6_6") (pintype "passive"))
    )
    (net (code "28") (name "Net-(C18-Pad2)") (class "Default")
      (node (ref "C18") (pin "2") (pinfunction "2_2") (pintype "passive"))
      (node (ref "T4") (pin "3") (pinfunction "3_3") (pintype "passive"))
    )
    (net (code "29") (name "Net-(C22-Pad2)") (class "Default")
      (node (ref "C22") (pin "2") (pinfunction "2_2") (pintype "passive"))
      (node (ref "T5") (pin "6") (pinfunction "6_6") (pintype "passive"))
    )
    (net (code "30") (name "Net-(IC4-RF_IN)") (class "Default")
      (node (ref "C10") (pin "1") (pinfunction "1_1") (pintype "passive"))
      (node (ref "IC4") (pin "5") (pinfunction "RF_IN_5") (pintype "input"))
    )
    (net (code "31") (name "Net-(IC4-RF_OUT1)") (class "Default")
      (node (ref "C9") (pin "2") (pinfunction "2_2") (pintype "passive"))
      (node (ref "IC4") (pin "1") (pinfunction "RF_OUT1_1") (pintype "output"))
    )
    (net (code "32") (name "Net-(IC4-RF_OUT2)") (class "Default")
      (node (ref "C13") (pin "1") (pinfunction "1_1") (pintype "passive"))
      (node (ref "IC4") (pin "3") (pinfunction "RF_OUT2_3") (pintype "output"))
    )
    (net (code "33") (name "Net-(IC5-RF_IN)") (class "Default")
      (node (ref "C18") (pin "1") (pinfunction "1_1") (pintype "passive"))
      (node (ref "IC5") (pin "5") (pinfunction "RF_IN_5") (pintype "input"))
    )
    (net (code "34") (name "Net-(IC5-RF_OUT1)") (class "Default")
      (node (ref "C15") (pin "2") (pinfunction "2_2") (pintype "passive"))
      (node (ref "IC5") (pin "1") (pinfunction "RF_OUT1_1") (pintype "output"))
    )
    (net (code "35") (name "Net-(IC5-RF_OUT2)") (class "Default")
      (node (ref "C19") (pin "2") (pinfunction "2_2") (pintype "passive"))
      (node (ref "IC5") (pin "3") (pinfunction "RF_OUT2_3") (pintype "output"))
    )
    (net (code "36") (name "Net-(J1-X)") (class "Default")
      (node (ref "C6") (pin "1") (pinfunction "1_1") (pintype "passive"))
      (node (ref "J1") (pin "1") (pinfunction "X_1") (pintype "passive"))
    )
    (net (code "37") (name "Net-(J2-X)") (class "Default")
      (node (ref "C9") (pin "1") (pinfunction "1_1") (pintype "passive"))
      (node (ref "J2") (pin "1") (pinfunction "X_1") (pintype "passive"))
    )
    (net (code "38") (name "Net-(J3-X)") (class "Default")
      (node (ref "C14") (pin "1") (pinfunction "1_1") (pintype "passive"))
      (node (ref "J3") (pin "1") (pinfunction "X_1") (pintype "passive"))
    )
    (net (code "39") (name "Net-(J4-X)") (class "Default")
      (node (ref "C19") (pin "1") (pinfunction "1_1") (pintype "passive"))
      (node (ref "J4") (pin "1") (pinfunction "X_1") (pintype "passive"))
    )
    (net (code "40") (name "Net-(J5-X)") (class "Default")
      (node (ref "C22") (pin "1") (pinfunction "1_1") (pintype "passive"))
      (node (ref "J5") (pin "1") (pinfunction "X_1") (pintype "passive"))
    )
    (net (code "41") (name "Net-(MN1-Pad1)") (class "Default")
      (node (ref "MN1") (pin "1") (pinfunction "1_1") (pintype "passive"))
      (node (ref "MN3") (pin "2") (pinfunction "2_2") (pintype "passive"))
    )
    (net (code "42") (name "Net-(MN2-Pad1)") (class "Default")
      (node (ref "MN2") (pin "1") (pinfunction "1_1") (pintype "passive"))
      (node (ref "MN4") (pin "2") (pinfunction "2_2") (pintype "passive"))
    )
    (net (code "43") (name "Net-(MN10-Pad1)") (class "Default")
      (node (ref "MN10") (pin "1") (pinfunction "1_1") (pintype "passive"))
      (node (ref "MN12") (pin "2") (pinfunction "2_2") (pintype "passive"))
    )
    (net (code "44") (name "Net-(MN11-Pad2)") (class "Default")
      (node (ref "MN11") (pin "2") (pinfunction "2_2") (pintype "passive"))
      (node (ref "MN9") (pin "1") (pinfunction "1_1") (pintype "passive"))
    )
    (net (code "45") (name "Net-(VT1-D)") (class "Default")
      (node (ref "C15") (pin "1") (pinfunction "1_1") (pintype "passive"))
      (node (ref "RA1") (pin "2") (pinfunction "2_2") (pintype "passive"))
      (node (ref "RA3") (pin "2") (pinfunction "2_2") (pintype "passive"))
      (node (ref "VT1") (pin "2") (pinfunction "D_2") (pintype "passive"))
    )
    (net (code "46") (name "Net-(VT1-G1)") (class "Default")
      (node (ref "R16") (pin "2") (pinfunction "2_2") (pintype "passive"))
      (node (ref "VT1") (pin "3") (pinfunction "G2_3") (pintype "passive"))
      (node (ref "VT1") (pin "4") (pinfunction "G1_4") (pintype "passive"))
    )
    (net (code "47") (name "Net-(VT2-D)") (class "Default")
      (node (ref "C13") (pin "2") (pinfunction "2_2") (pintype "passive"))
      (node (ref "R14") (pin "1") (pinfunction "1_1") (pintype "passive"))
      (node (ref "RA1") (pin "1") (pinfunction "1_1") (pintype "passive"))
      (node (ref "RA2") (pin "2") (pinfunction "2_2") (pintype "passive"))
      (node (ref "VT2") (pin "2") (pinfunction "D_2") (pintype "passive"))
    )
    (net (code "48") (name "Net-(VT2-G1)") (class "Default")
      (node (ref "R15") (pin "1") (pinfunction "1_1") (pintype "passive"))
      (node (ref "VT2") (pin "3") (pinfunction "G2_3") (pintype "passive"))
      (node (ref "VT2") (pin "4") (pinfunction "G1_4") (pintype "passive"))
    )
    (net (code "49") (name "VCC1P8_LMS") (class "Default")
      (node (ref "C4") (pin "2") (pinfunction "2_2") (pintype "passive"))
      (node (ref "C5") (pin "2") (pinfunction "2_2") (pintype "passive"))
      (node (ref "C7") (pin "2") (pinfunction "2_2") (pintype "passive"))
      (node (ref "C8") (pin "2") (pinfunction "2_2") (pintype "passive"))
      (node (ref "MN1") (pin "2") (pinfunction "2_2") (pintype "passive"))
      (node (ref "MN10") (pin "2") (pinfunction "2_2") (pintype "passive"))
      (node (ref "MN2") (pin "2") (pinfunction "2_2") (pintype "passive"))
      (node (ref "MN9") (pin "2") (pinfunction "2_2") (pintype "passive"))
      (node (ref "R14") (pin "2") (pinfunction "2_2") (pintype "passive"))
    )
  )
)
